# dual_encoder_shield_revA.net
KiCad netlist of a schematic drawn in EAGLE
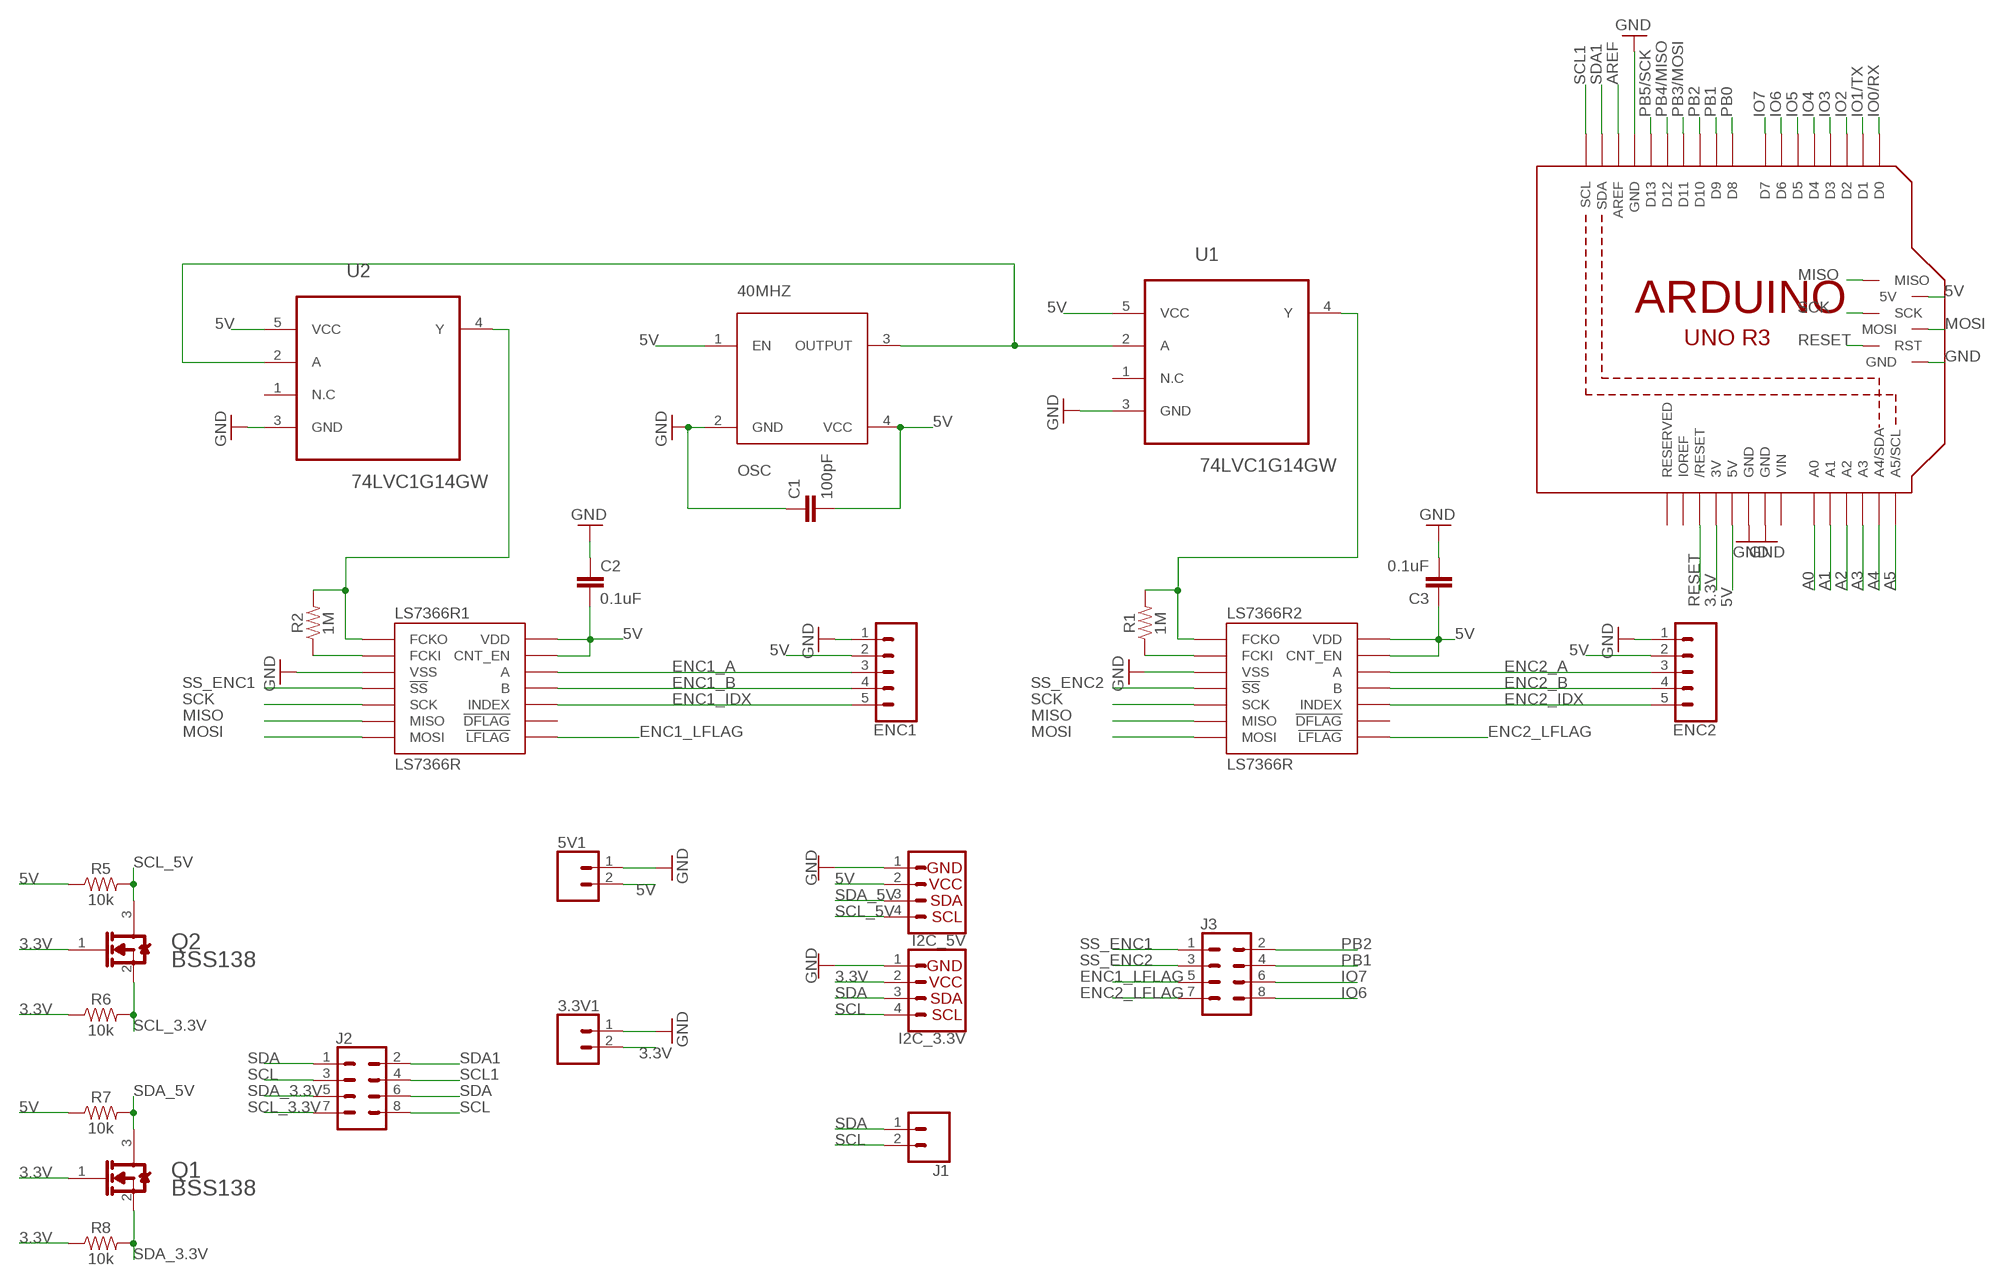
[diagram p0: schematic, sheet 1]

(export (version "E")
  (design (tool "Eeschema 10.0.6"))
  (components
    (comp (ref "3.3V1")
      (value "CONN_02-JST-2MM-SMT")
      (footprint "eagle-import:JST-2-SMD")
      (libsource (lib "eagle-import") (part "CONN_02-JST-2MM-SMT"))
    )
    (comp (ref "5V1")
      (value "CONN_02-JST-2MM-SMT")
      (footprint "eagle-import:JST-2-SMD")
      (libsource (lib "eagle-import") (part "CONN_02-JST-2MM-SMT"))
    )
    (comp (ref "40MHZ")
      (value "OSC")
      (footprint "eagle-import:CB3OSCILLATOR")
      (libsource (lib "eagle-import") (part "OSC"))
    )
    (comp (ref "C1")
      (value "100pF")
      (footprint "eagle-import:0603")
      (libsource (lib "eagle-import") (part "100PF-0603-50V-5%"))
    )
    (comp (ref "C2")
      (value "0.1uF")
      (footprint "eagle-import:0603")
      (libsource (lib "eagle-import") (part "0.1UF-0603-25V-5%"))
    )
    (comp (ref "C3")
      (value "0.1uF")
      (footprint "eagle-import:0603")
      (libsource (lib "eagle-import") (part "0.1UF-0603-25V-5%"))
    )
    (comp (ref "ENC1")
      (value "CONN_05")
      (footprint "eagle-import:1X05")
      (libsource (lib "eagle-import") (part "CONN_05"))
    )
    (comp (ref "ENC2")
      (value "CONN_05")
      (footprint "eagle-import:1X05")
      (libsource (lib "eagle-import") (part "CONN_05"))
    )
    (comp (ref "I2C_3.3V")
      (value "QWIIC_CONNECTORJS-1MM")
      (footprint "eagle-import:JST04_1MM_RA")
      (libsource (lib "eagle-import") (part "QWIIC_CONNECTORJS-1MM"))
    )
    (comp (ref "I2C_5V")
      (value "QWIIC_CONNECTORJS-1MM")
      (footprint "eagle-import:JST04_1MM_RA")
      (libsource (lib "eagle-import") (part "QWIIC_CONNECTORJS-1MM"))
    )
    (comp (ref "J1")
      (value "CONN_02")
      (footprint "eagle-import:1X02")
      (libsource (lib "eagle-import") (part "CONN_02"))
    )
    (comp (ref "J2")
      (value "CONN_04X2")
      (footprint "eagle-import:2X4")
      (libsource (lib "eagle-import") (part "CONN_04X2"))
    )
    (comp (ref "J3")
      (value "CONN_04X2")
      (footprint "eagle-import:2X4")
      (libsource (lib "eagle-import") (part "CONN_04X2"))
    )
    (comp (ref "LS7366R1")
      (value "LS7366R")
      (footprint "eagle-import:SOIC14")
      (fields (field (name "MF") "LSI"))
      (libsource (lib "eagle-import") (part "LS7366R"))
    )
    (comp (ref "LS7366R2")
      (value "LS7366R")
      (footprint "eagle-import:SOIC14")
      (fields (field (name "MF") "LSI"))
      (libsource (lib "eagle-import") (part "LS7366R"))
    )
    (comp (ref "M1")
      (value "ARDUINO_R3_ICSP")
      (footprint "eagle-import:ARDUINOR3_ICSP")
      (libsource (lib "eagle-import") (part "ARDUINO_R3_ICSP"))
    )
    (comp (ref "Q1")
      (value "ON_SEMI_BSS138ON_SEMI_BSS138_0_0")
      (footprint "eagle-import:ON_SEMI_BSS138_0")
      (fields
        (field (name "DIGIKEY_PART_NUMBER") "BSS138CT-ND")
        (field (name "MF") "ON Semi")
        (field (name "MOUSER_PART_NUMBER") "512-BSS138")
      )
      (libsource (lib "eagle-import") (part "ON_SEMI_BSS138ON_SEMI_BSS138_0_0"))
    )
    (comp (ref "Q2")
      (value "ON_SEMI_BSS138ON_SEMI_BSS138_0_0")
      (footprint "eagle-import:ON_SEMI_BSS138_0")
      (fields
        (field (name "DIGIKEY_PART_NUMBER") "BSS138CT-ND")
        (field (name "MF") "ON Semi")
        (field (name "MOUSER_PART_NUMBER") "512-BSS138")
      )
      (libsource (lib "eagle-import") (part "ON_SEMI_BSS138ON_SEMI_BSS138_0_0"))
    )
    (comp (ref "R1")
      (value "1M")
      (footprint "eagle-import:0603")
      (libsource (lib "eagle-import") (part "1MOHM-0603-1/4W-5%"))
    )
    (comp (ref "R2")
      (value "1M")
      (footprint "eagle-import:0603")
      (libsource (lib "eagle-import") (part "1MOHM-0603-1/4W-5%"))
    )
    (comp (ref "R5")
      (value "10k")
      (footprint "eagle-import:0603")
      (libsource (lib "eagle-import") (part "10KOHM-0603-1/10W-1%"))
    )
    (comp (ref "R6")
      (value "10k")
      (footprint "eagle-import:0603")
      (libsource (lib "eagle-import") (part "10KOHM-0603-1/10W-1%"))
    )
    (comp (ref "R7")
      (value "10k")
      (footprint "eagle-import:0603")
      (libsource (lib "eagle-import") (part "10KOHM-0603-1/10W-1%"))
    )
    (comp (ref "R8")
      (value "10k")
      (footprint "eagle-import:0603")
      (libsource (lib "eagle-import") (part "10KOHM-0603-1/10W-1%"))
    )
    (comp (ref "U1")
      (value "74LVC1G14GW")
      (footprint "eagle-import:SOT65P210X110-5N")
      (fields (field (name "MF") "NXP Semiconductors"))
      (libsource (lib "eagle-import") (part "74LVC1G14GW"))
    )
    (comp (ref "U2")
      (value "74LVC1G14GW")
      (footprint "eagle-import:SOT65P210X110-5N")
      (fields (field (name "MF") "NXP Semiconductors"))
      (libsource (lib "eagle-import") (part "74LVC1G14GW"))
    )
  )
  (nets
    (net (code "1") (name "/3.3V") (class "Default")
      (node (ref "3.3V1") (pin "2") (pinfunction "1_2") (pintype "passive"))
      (node (ref "I2C_3.3V") (pin "2") (pinfunction "2_2") (pintype "power_in"))
      (node (ref "M1") (pin "3V") (pinfunction "3V_3V") (pintype "power_in"))
      (node (ref "Q1") (pin "1") (pinfunction "G_1") (pintype "bidirectional"))
      (node (ref "Q2") (pin "1") (pinfunction "G_1") (pintype "bidirectional"))
      (node (ref "R6") (pin "1") (pinfunction "1_1") (pintype "passive"))
      (node (ref "R8") (pin "1") (pinfunction "1_1") (pintype "passive"))
    )
    (net (code "2") (name "/5V") (class "Default")
      (node (ref "40MHZ") (pin "1") (pinfunction "EN_1") (pintype "input"))
      (node (ref "40MHZ") (pin "4") (pinfunction "VCC_4") (pintype "input"))
      (node (ref "5V1") (pin "2") (pinfunction "1_2") (pintype "passive"))
      (node (ref "C1") (pin "2") (pinfunction "2_2") (pintype "passive"))
      (node (ref "C2") (pin "2") (pinfunction "2_2") (pintype "passive"))
      (node (ref "C3") (pin "1") (pinfunction "1_1") (pintype "passive"))
      (node (ref "ENC1") (pin "2") (pinfunction "2_2") (pintype "passive"))
      (node (ref "ENC2") (pin "2") (pinfunction "2_2") (pintype "passive"))
      (node (ref "I2C_5V") (pin "2") (pinfunction "2_2") (pintype "power_in"))
      (node (ref "LS7366R1") (pin "13") (pinfunction "CNT_EN_13") (pintype "bidirectional"))
      (node (ref "LS7366R1") (pin "14") (pinfunction "VDD_14") (pintype "bidirectional"))
      (node (ref "LS7366R2") (pin "13") (pinfunction "CNT_EN_13") (pintype "bidirectional"))
      (node (ref "LS7366R2") (pin "14") (pinfunction "VDD_14") (pintype "bidirectional"))
      (node (ref "M1") (pin "5V") (pinfunction "5V_5V") (pintype "power_in"))
      (node (ref "M1") (pin "5V_ICSP") (pinfunction "5V_5V_ICSP") (pintype "passive"))
      (node (ref "R5") (pin "1") (pinfunction "1_1") (pintype "passive"))
      (node (ref "R7") (pin "1") (pinfunction "1_1") (pintype "passive"))
      (node (ref "U1") (pin "5") (pinfunction "VCC_5") (pintype "power_in"))
      (node (ref "U2") (pin "5") (pinfunction "VCC_5") (pintype "power_in"))
    )
    (net (code "3") (name "/A0") (class "Default")
      (node (ref "M1") (pin "A0") (pinfunction "A0_A0") (pintype "bidirectional"))
    )
    (net (code "4") (name "/A1") (class "Default")
      (node (ref "M1") (pin "A1") (pinfunction "A1_A1") (pintype "bidirectional"))
    )
    (net (code "5") (name "/A2") (class "Default")
      (node (ref "M1") (pin "A2") (pinfunction "A2_A2") (pintype "bidirectional"))
    )
    (net (code "6") (name "/A3") (class "Default")
      (node (ref "M1") (pin "A3") (pinfunction "A3_A3") (pintype "bidirectional"))
    )
    (net (code "7") (name "/A4") (class "Default")
      (node (ref "M1") (pin "A4") (pinfunction "A4/SDA_A4") (pintype "bidirectional"))
    )
    (net (code "8") (name "/A5") (class "Default")
      (node (ref "M1") (pin "A5") (pinfunction "A5/SCL_A5") (pintype "bidirectional"))
    )
    (net (code "9") (name "/AREF") (class "Default")
      (node (ref "M1") (pin "AREF") (pinfunction "AREF_AREF") (pintype "bidirectional"))
    )
    (net (code "10") (name "/ENC1_A") (class "Default")
      (node (ref "ENC1") (pin "3") (pinfunction "3_3") (pintype "passive"))
      (node (ref "LS7366R1") (pin "12") (pinfunction "A_12") (pintype "bidirectional"))
    )
    (net (code "11") (name "/ENC1_B") (class "Default")
      (node (ref "ENC1") (pin "4") (pinfunction "4_4") (pintype "passive"))
      (node (ref "LS7366R1") (pin "11") (pinfunction "B_11") (pintype "bidirectional"))
    )
    (net (code "12") (name "/ENC1_IDX") (class "Default")
      (node (ref "ENC1") (pin "5") (pinfunction "5_5") (pintype "passive"))
      (node (ref "LS7366R1") (pin "10") (pinfunction "INDEX_10") (pintype "bidirectional"))
    )
    (net (code "13") (name "/ENC1_LFLAG") (class "Default")
      (node (ref "J3") (pin "5") (pinfunction "5_5") (pintype "passive"))
      (node (ref "LS7366R1") (pin "8") (pinfunction "~{LFLAG}_8") (pintype "bidirectional"))
    )
    (net (code "14") (name "/ENC2_A") (class "Default")
      (node (ref "ENC2") (pin "3") (pinfunction "3_3") (pintype "passive"))
      (node (ref "LS7366R2") (pin "12") (pinfunction "A_12") (pintype "bidirectional"))
    )
    (net (code "15") (name "/ENC2_B") (class "Default")
      (node (ref "ENC2") (pin "4") (pinfunction "4_4") (pintype "passive"))
      (node (ref "LS7366R2") (pin "11") (pinfunction "B_11") (pintype "bidirectional"))
    )
    (net (code "16") (name "/ENC2_IDX") (class "Default")
      (node (ref "ENC2") (pin "5") (pinfunction "5_5") (pintype "passive"))
      (node (ref "LS7366R2") (pin "10") (pinfunction "INDEX_10") (pintype "bidirectional"))
    )
    (net (code "17") (name "/ENC2_LFLAG") (class "Default")
      (node (ref "J3") (pin "7") (pinfunction "7_7") (pintype "passive"))
      (node (ref "LS7366R2") (pin "8") (pinfunction "~{LFLAG}_8") (pintype "bidirectional"))
    )
    (net (code "18") (name "/IO0{slash}RX") (class "Default")
      (node (ref "M1") (pin "D0") (pinfunction "D0_D0") (pintype "bidirectional"))
    )
    (net (code "19") (name "/IO1{slash}TX") (class "Default")
      (node (ref "M1") (pin "D1") (pinfunction "D1_D1") (pintype "bidirectional"))
    )
    (net (code "20") (name "/IO2") (class "Default")
      (node (ref "M1") (pin "D2") (pinfunction "D2_D2") (pintype "bidirectional"))
    )
    (net (code "21") (name "/IO3") (class "Default")
      (node (ref "M1") (pin "D3") (pinfunction "D3_D3") (pintype "bidirectional"))
    )
    (net (code "22") (name "/IO4") (class "Default")
      (node (ref "M1") (pin "D4") (pinfunction "D4_D4") (pintype "bidirectional"))
    )
    (net (code "23") (name "/IO5") (class "Default")
      (node (ref "M1") (pin "D5") (pinfunction "D5_D5") (pintype "bidirectional"))
    )
    (net (code "24") (name "/IO6") (class "Default")
      (node (ref "J3") (pin "8") (pinfunction "8_8") (pintype "passive"))
      (node (ref "M1") (pin "D6") (pinfunction "D6_D6") (pintype "bidirectional"))
    )
    (net (code "25") (name "/IO7") (class "Default")
      (node (ref "J3") (pin "6") (pinfunction "6_6") (pintype "passive"))
      (node (ref "M1") (pin "D7") (pinfunction "D7_D7") (pintype "bidirectional"))
    )
    (net (code "26") (name "/MISO") (class "Default")
      (node (ref "LS7366R1") (pin "6") (pinfunction "MISO_6") (pintype "bidirectional"))
      (node (ref "LS7366R2") (pin "6") (pinfunction "MISO_6") (pintype "bidirectional"))
      (node (ref "M1") (pin "MISO") (pinfunction "MISO_MISO") (pintype "passive"))
    )
    (net (code "27") (name "/MOSI") (class "Default")
      (node (ref "LS7366R1") (pin "7") (pinfunction "MOSI_7") (pintype "bidirectional"))
      (node (ref "LS7366R2") (pin "7") (pinfunction "MOSI_7") (pintype "bidirectional"))
      (node (ref "M1") (pin "MOSI") (pinfunction "MOSI_MOSI") (pintype "passive"))
    )
    (net (code "28") (name "/PB0") (class "Default")
      (node (ref "M1") (pin "D8") (pinfunction "D8_D8") (pintype "bidirectional"))
    )
    (net (code "29") (name "/PB1") (class "Default")
      (node (ref "J3") (pin "4") (pinfunction "4_4") (pintype "passive"))
      (node (ref "M1") (pin "D9") (pinfunction "D9_D9") (pintype "bidirectional"))
    )
    (net (code "30") (name "/PB2") (class "Default")
      (node (ref "J3") (pin "2") (pinfunction "2_2") (pintype "passive"))
      (node (ref "M1") (pin "D10") (pinfunction "D10_D10") (pintype "bidirectional"))
    )
    (net (code "31") (name "/PB3{slash}MOSI") (class "Default")
      (node (ref "M1") (pin "D11") (pinfunction "D11_D11") (pintype "bidirectional"))
    )
    (net (code "32") (name "/PB4{slash}MISO") (class "Default")
      (node (ref "M1") (pin "D12") (pinfunction "D12_D12") (pintype "bidirectional"))
    )
    (net (code "33") (name "/PB5{slash}SCK") (class "Default")
      (node (ref "M1") (pin "D13") (pinfunction "D13_D13") (pintype "bidirectional"))
    )
    (net (code "34") (name "/RESET") (class "Default")
      (node (ref "M1") (pin "RESET") (pinfunction "/RESET_RESET") (pintype "bidirectional"))
      (node (ref "M1") (pin "RESET_ICSP") (pinfunction "RST_RESET_ICSP") (pintype "passive"))
    )
    (net (code "35") (name "/SCK") (class "Default")
      (node (ref "LS7366R1") (pin "5") (pinfunction "SCK_5") (pintype "bidirectional"))
      (node (ref "LS7366R2") (pin "5") (pinfunction "SCK_5") (pintype "bidirectional"))
      (node (ref "M1") (pin "SCK") (pinfunction "SCK_SCK") (pintype "passive"))
    )
    (net (code "36") (name "/SCL") (class "Default")
      (node (ref "I2C_3.3V") (pin "4") (pinfunction "4_4") (pintype "passive"))
      (node (ref "J1") (pin "2") (pinfunction "2_2") (pintype "passive"))
      (node (ref "J2") (pin "3") (pinfunction "3_3") (pintype "passive"))
      (node (ref "J2") (pin "8") (pinfunction "8_8") (pintype "passive"))
    )
    (net (code "37") (name "/SCL1") (class "Default")
      (node (ref "J2") (pin "4") (pinfunction "4_4") (pintype "passive"))
      (node (ref "M1") (pin "SCL") (pinfunction "SCL_SCL") (pintype "bidirectional"))
    )
    (net (code "38") (name "/SCL_3.3V") (class "Default")
      (node (ref "J2") (pin "7") (pinfunction "7_7") (pintype "passive"))
      (node (ref "Q2") (pin "2") (pinfunction "S_2") (pintype "bidirectional"))
      (node (ref "R6") (pin "2") (pinfunction "2_2") (pintype "passive"))
    )
    (net (code "39") (name "/SCL_5V") (class "Default")
      (node (ref "I2C_5V") (pin "4") (pinfunction "4_4") (pintype "passive"))
      (node (ref "Q2") (pin "3") (pinfunction "D_3") (pintype "bidirectional"))
      (node (ref "R5") (pin "2") (pinfunction "2_2") (pintype "passive"))
    )
    (net (code "40") (name "/SDA") (class "Default")
      (node (ref "I2C_3.3V") (pin "3") (pinfunction "3_3") (pintype "passive"))
      (node (ref "J1") (pin "1") (pinfunction "1_1") (pintype "passive"))
      (node (ref "J2") (pin "1") (pinfunction "1_1") (pintype "passive"))
      (node (ref "J2") (pin "6") (pinfunction "6_6") (pintype "passive"))
    )
    (net (code "41") (name "/SDA1") (class "Default")
      (node (ref "J2") (pin "2") (pinfunction "2_2") (pintype "passive"))
      (node (ref "M1") (pin "SDA") (pinfunction "SDA_SDA") (pintype "bidirectional"))
    )
    (net (code "42") (name "/SDA_3.3V") (class "Default")
      (node (ref "J2") (pin "5") (pinfunction "5_5") (pintype "passive"))
      (node (ref "Q1") (pin "2") (pinfunction "S_2") (pintype "bidirectional"))
      (node (ref "R8") (pin "2") (pinfunction "2_2") (pintype "passive"))
    )
    (net (code "43") (name "/SDA_5V") (class "Default")
      (node (ref "I2C_5V") (pin "3") (pinfunction "3_3") (pintype "passive"))
      (node (ref "Q1") (pin "3") (pinfunction "D_3") (pintype "bidirectional"))
      (node (ref "R7") (pin "2") (pinfunction "2_2") (pintype "passive"))
    )
    (net (code "44") (name "/SS_ENC1") (class "Default")
      (node (ref "J3") (pin "1") (pinfunction "1_1") (pintype "passive"))
      (node (ref "LS7366R1") (pin "4") (pinfunction "~{SS}_4") (pintype "bidirectional"))
    )
    (net (code "45") (name "/SS_ENC2") (class "Default")
      (node (ref "J3") (pin "3") (pinfunction "3_3") (pintype "passive"))
      (node (ref "LS7366R2") (pin "4") (pinfunction "~{SS}_4") (pintype "bidirectional"))
    )
    (net (code "46") (name "/VIN") (class "Default")
      (node (ref "M1") (pin "VIN") (pinfunction "VIN_VIN") (pintype "power_in"))
    )
    (net (code "47") (name "GND") (class "Default")
      (node (ref "3.3V1") (pin "1") (pinfunction "2_1") (pintype "passive"))
      (node (ref "40MHZ") (pin "2") (pinfunction "GND_2") (pintype "input"))
      (node (ref "5V1") (pin "1") (pinfunction "2_1") (pintype "passive"))
      (node (ref "C1") (pin "1") (pinfunction "1_1") (pintype "passive"))
      (node (ref "C2") (pin "1") (pinfunction "1_1") (pintype "passive"))
      (node (ref "C3") (pin "2") (pinfunction "2_2") (pintype "passive"))
      (node (ref "ENC1") (pin "1") (pinfunction "1_1") (pintype "passive"))
      (node (ref "ENC2") (pin "1") (pinfunction "1_1") (pintype "passive"))
      (node (ref "I2C_3.3V") (pin "1") (pinfunction "1_1") (pintype "power_in"))
      (node (ref "I2C_5V") (pin "1") (pinfunction "1_1") (pintype "power_in"))
      (node (ref "LS7366R1") (pin "3") (pinfunction "VSS_3") (pintype "bidirectional"))
      (node (ref "LS7366R2") (pin "3") (pinfunction "VSS_3") (pintype "bidirectional"))
      (node (ref "M1") (pin "GND") (pinfunction "GND_GND") (pintype "power_in"))
      (node (ref "M1") (pin "GND@1") (pinfunction "GND_GND@1") (pintype "power_in"))
      (node (ref "M1") (pin "GND@2") (pinfunction "GND_GND@2") (pintype "passive"))
      (node (ref "M1") (pin "GND@3") (pinfunction "GND_GND@3") (pintype "power_in"))
      (node (ref "U1") (pin "3") (pinfunction "GND_3") (pintype "passive"))
      (node (ref "U2") (pin "3") (pinfunction "GND_3") (pintype "passive"))
    )
    (net (code "48") (name "Net-(40MHZ-OUTPUT)") (class "Default")
      (node (ref "40MHZ") (pin "3") (pinfunction "OUTPUT_3") (pintype "output"))
      (node (ref "U1") (pin "2") (pinfunction "A_2") (pintype "input"))
      (node (ref "U2") (pin "2") (pinfunction "A_2") (pintype "input"))
    )
    (net (code "49") (name "Net-(LS7366R1-FCKI)") (class "Default")
      (node (ref "LS7366R1") (pin "2") (pinfunction "FCKI_2") (pintype "bidirectional"))
      (node (ref "R2") (pin "1") (pinfunction "1_1") (pintype "passive"))
    )
    (net (code "50") (name "Net-(LS7366R1-FCKO)") (class "Default")
      (node (ref "LS7366R1") (pin "1") (pinfunction "FCKO_1") (pintype "bidirectional"))
      (node (ref "R2") (pin "2") (pinfunction "2_2") (pintype "passive"))
      (node (ref "U2") (pin "4") (pinfunction "Y_4") (pintype "output"))
    )
    (net (code "51") (name "Net-(LS7366R2-FCKI)") (class "Default")
      (node (ref "LS7366R2") (pin "2") (pinfunction "FCKI_2") (pintype "bidirectional"))
      (node (ref "R1") (pin "1") (pinfunction "1_1") (pintype "passive"))
    )
    (net (code "52") (name "Net-(LS7366R2-FCKO)") (class "Default")
      (node (ref "LS7366R2") (pin "1") (pinfunction "FCKO_1") (pintype "bidirectional"))
      (node (ref "R1") (pin "2") (pinfunction "2_2") (pintype "passive"))
      (node (ref "U1") (pin "4") (pinfunction "Y_4") (pintype "output"))
    )
    (net (code "53") (name "unconnected-(LS7366R1-~{DFLAG}-Pad9)") (class "Default")
      (node (ref "LS7366R1") (pin "9") (pinfunction "~{DFLAG}_9") (pintype "bidirectional"))
    )
    (net (code "54") (name "unconnected-(LS7366R2-~{DFLAG}-Pad9)") (class "Default")
      (node (ref "LS7366R2") (pin "9") (pinfunction "~{DFLAG}_9") (pintype "bidirectional"))
    )
    (net (code "55") (name "unconnected-(M1-PadIOREF)") (class "Default")
      (node (ref "M1") (pin "IOREF") (pinfunction "IOREF_IOREF") (pintype "output"))
    )
    (net (code "56") (name "unconnected-(M1-PadRESERVED)") (class "Default")
      (node (ref "M1") (pin "RESERVED") (pinfunction "RESERVED_RESERVED") (pintype "no_connect"))
    )
    (net (code "57") (name "unconnected-(U1-N.C-Pad1)") (class "Default")
      (node (ref "U1") (pin "1") (pinfunction "N.C_1") (pintype "no_connect"))
    )
    (net (code "58") (name "unconnected-(U2-N.C-Pad1)") (class "Default")
      (node (ref "U2") (pin "1") (pinfunction "N.C_1") (pintype "no_connect"))
    )
  )
)
